# assignment3.net
KiCad netlist of a schematic drawn in EAGLE
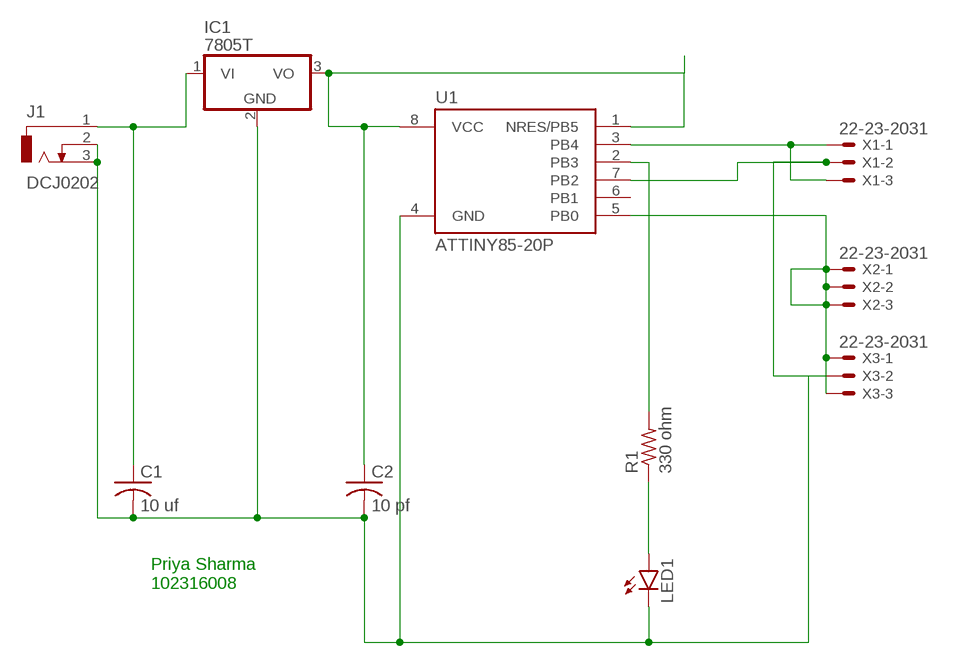
[diagram p0: schematic, sheet 1]

(export (version "E")
  (design (tool "Eeschema 10.0.6"))
  (components
    (comp (ref "C1")
      (value "10 uf")
      (footprint "eagle-import:C025-024X044")
      (libsource (lib "eagle-import") (part "C-US025-024X044"))
    )
    (comp (ref "C2")
      (value "10 pf")
      (footprint "eagle-import:C025-024X044")
      (libsource (lib "eagle-import") (part "C-US025-024X044"))
    )
    (comp (ref "IC1")
      (value "7805T")
      (footprint "eagle-import:TO220H")
      (libsource (lib "eagle-import") (part "78T05"))
    )
    (comp (ref "J1")
      (value "DCJ0202")
      (footprint "eagle-import:DCJ0202")
      (libsource (lib "eagle-import") (part "DCJ0202"))
    )
    (comp (ref "LED1")
      (value "LED3MM")
      (footprint "eagle-import:LED3MM")
      (libsource (lib "eagle-import") (part "LED3MM"))
    )
    (comp (ref "R1")
      (value "330 ohm")
      (footprint "eagle-import:0207_5V")
      (libsource (lib "eagle-import") (part "R-US_0207/5V"))
    )
    (comp (ref "U1")
      (value "ATTINY85-20P")
      (footprint "eagle-import:PDIP08_300MIL")
      (libsource (lib "eagle-import") (part "ATTINY85P-20"))
    )
    (comp (ref "X1")
      (value "22-23-2031")
      (footprint "eagle-import:22-23-2031")
      (fields (field (name "MF") "MOLEX"))
      (libsource (lib "eagle-import") (part "22-23-2031"))
    )
    (comp (ref "X2")
      (value "22-23-2031")
      (footprint "eagle-import:22-23-2031")
      (fields (field (name "MF") "MOLEX"))
      (libsource (lib "eagle-import") (part "22-23-2031"))
    )
    (comp (ref "X3")
      (value "22-23-2031")
      (footprint "eagle-import:22-23-2031")
      (fields (field (name "MF") "MOLEX"))
      (libsource (lib "eagle-import") (part "22-23-2031"))
    )
  )
  (nets
    (net (code "1") (name "Net-(IC1-GND)") (class "Default")
      (node (ref "C1") (pin "2") (pinfunction "2_2") (pintype "passive"))
      (node (ref "C2") (pin "2") (pinfunction "2_2") (pintype "passive"))
      (node (ref "IC1") (pin "2") (pinfunction "GND_2") (pintype "passive"))
      (node (ref "J1") (pin "2") (pinfunction "2_2") (pintype "passive"))
      (node (ref "J1") (pin "3") (pinfunction "3_3") (pintype "passive"))
      (node (ref "LED1") (pin "K") (pinfunction "C_K") (pintype "passive"))
      (node (ref "U1") (pin "4") (pinfunction "GND_4") (pintype "power_in"))
    )
    (net (code "2") (name "Net-(IC1-VI)") (class "Default")
      (node (ref "C1") (pin "1") (pinfunction "1_1") (pintype "passive"))
      (node (ref "IC1") (pin "1") (pinfunction "VI_1") (pintype "input"))
      (node (ref "J1") (pin "1") (pinfunction "1_1") (pintype "passive"))
    )
    (net (code "3") (name "Net-(IC1-VO)") (class "Default")
      (node (ref "C2") (pin "1") (pinfunction "1_1") (pintype "passive"))
      (node (ref "IC1") (pin "3") (pinfunction "VO_3") (pintype "passive"))
      (node (ref "U1") (pin "1") (pinfunction "NRES/PB5_1") (pintype "bidirectional"))
      (node (ref "U1") (pin "8") (pinfunction "VCC_8") (pintype "power_in"))
    )
    (net (code "4") (name "Net-(LED1-PadA)") (class "Default")
      (node (ref "LED1") (pin "A") (pinfunction "A_A") (pintype "passive"))
      (node (ref "R1") (pin "1") (pinfunction "1_1") (pintype "passive"))
    )
    (net (code "5") (name "Net-(U1-PB0)") (class "Default")
      (node (ref "U1") (pin "5") (pinfunction "PB0_5") (pintype "bidirectional"))
      (node (ref "X2") (pin "1") (pinfunction "S_1") (pintype "passive"))
      (node (ref "X2") (pin "2") (pinfunction "S_2") (pintype "passive"))
      (node (ref "X2") (pin "3") (pinfunction "S_3") (pintype "passive"))
      (node (ref "X3") (pin "1") (pinfunction "S_1") (pintype "passive"))
      (node (ref "X3") (pin "3") (pinfunction "S_3") (pintype "passive"))
    )
    (net (code "6") (name "Net-(U1-PB2)") (class "Default")
      (node (ref "U1") (pin "7") (pinfunction "PB2_7") (pintype "bidirectional"))
      (node (ref "X1") (pin "2") (pinfunction "S_2") (pintype "passive"))
      (node (ref "X3") (pin "2") (pinfunction "S_2") (pintype "passive"))
    )
    (net (code "7") (name "Net-(U1-PB3)") (class "Default")
      (node (ref "R1") (pin "2") (pinfunction "2_2") (pintype "passive"))
      (node (ref "U1") (pin "2") (pinfunction "PB3_2") (pintype "bidirectional"))
    )
    (net (code "8") (name "Net-(U1-PB4)") (class "Default")
      (node (ref "U1") (pin "3") (pinfunction "PB4_3") (pintype "bidirectional"))
      (node (ref "X1") (pin "1") (pinfunction "S_1") (pintype "passive"))
      (node (ref "X1") (pin "3") (pinfunction "S_3") (pintype "passive"))
    )
    (net (code "9") (name "unconnected-(U1-PB1-Pad6)") (class "Default")
      (node (ref "U1") (pin "6") (pinfunction "PB1_6") (pintype "bidirectional"))
    )
  )
)
